# Rectifier.net
KiCad netlist of a schematic drawn in Altium Designer
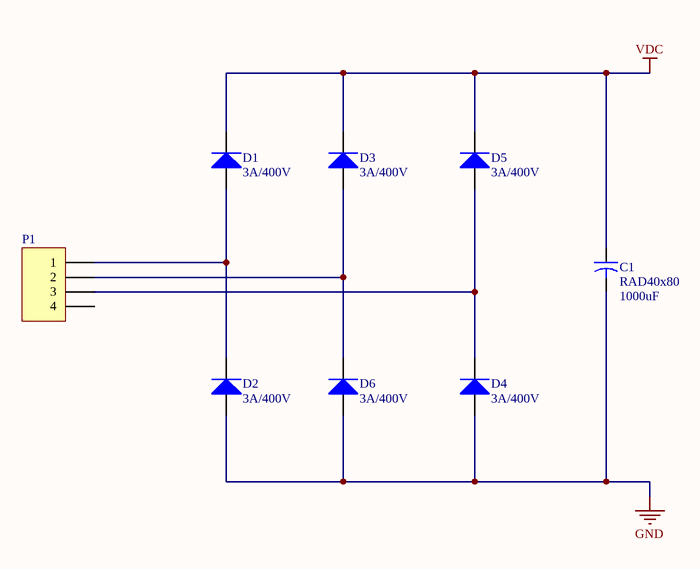
[diagram p0: Rectifier.SchDoc]

(export (version "E")
  (design (tool "Eeschema 10.0.6"))
  (components
    (comp (ref "C1")
      (value "1000uF")
      (footprint "RAD40x80")
      (description "CAP ALUM 1000UF 20% 450V RAD 40X80")
      (fields (field (name "MANUFACTURER") "UNITED CHEMI-CON") (field (name "PACKAGE REFERENCE") "RAD40x80"))
      (libsource (lib "CAPACITOR_LIB") (part "CAP ALUM 1000UF 20% 450V RAD 40X80"))
    )
    (comp (ref "D1")
      (value "3A/400V")
      (footprint "DO201AD")
      (description "DIODE GEN PURP 400V 3A DO201AD")
      (fields
        (field (name "MANUFACTURER") "DIODES INC.")
        (field (name "Comment") "DIODE GEN PURP 400V 3A DO201AD - 1N5404")
      )
      (libsource (lib "DISCRETE_LIB") (part "DIODE GEN PURP 400V 3A DO201AD - 1N5404"))
    )
    (comp (ref "D2")
      (value "3A/400V")
      (footprint "DO201AD")
      (description "DIODE GEN PURP 400V 3A DO201AD")
      (fields
        (field (name "MANUFACTURER") "DIODES INC.")
        (field (name "Comment") "DIODE GEN PURP 400V 3A DO201AD - 1N5404")
      )
      (libsource (lib "DISCRETE_LIB") (part "DIODE GEN PURP 400V 3A DO201AD - 1N5404"))
    )
    (comp (ref "D3")
      (value "3A/400V")
      (footprint "DO201AD")
      (description "DIODE GEN PURP 400V 3A DO201AD")
      (fields
        (field (name "MANUFACTURER") "DIODES INC.")
        (field (name "Comment") "DIODE GEN PURP 400V 3A DO201AD - 1N5404")
      )
      (libsource (lib "DISCRETE_LIB") (part "DIODE GEN PURP 400V 3A DO201AD - 1N5404"))
    )
    (comp (ref "D4")
      (value "3A/400V")
      (footprint "DO201AD")
      (description "DIODE GEN PURP 400V 3A DO201AD")
      (fields
        (field (name "MANUFACTURER") "DIODES INC.")
        (field (name "Comment") "DIODE GEN PURP 400V 3A DO201AD - 1N5404")
      )
      (libsource (lib "DISCRETE_LIB") (part "DIODE GEN PURP 400V 3A DO201AD - 1N5404"))
    )
    (comp (ref "D5")
      (value "3A/400V")
      (footprint "DO201AD")
      (description "DIODE GEN PURP 400V 3A DO201AD")
      (fields
        (field (name "MANUFACTURER") "DIODES INC.")
        (field (name "Comment") "DIODE GEN PURP 400V 3A DO201AD - 1N5404")
      )
      (libsource (lib "DISCRETE_LIB") (part "DIODE GEN PURP 400V 3A DO201AD - 1N5404"))
    )
    (comp (ref "D6")
      (value "3A/400V")
      (footprint "DO201AD")
      (description "DIODE GEN PURP 400V 3A DO201AD")
      (fields
        (field (name "MANUFACTURER") "DIODES INC.")
        (field (name "Comment") "DIODE GEN PURP 400V 3A DO201AD - 1N5404")
      )
      (libsource (lib "DISCRETE_LIB") (part "DIODE GEN PURP 400V 3A DO201AD - 1N5404"))
    )
    (comp (ref "P1")
      (value "CTB9358/4AO")
      (footprint "CTB9350/4AO")
      (description "4 pos plıggable terminal")
      (fields (field (name "PUBLISHER") "Sinan"))
      (libsource (lib "Viva") (part "CTB9358/4AO"))
    )
  )
  (nets
    (net (code "1") (name "GND") (class "Default")
      (node (ref "C1") (pin "2") (pinfunction "2_2") (pintype "passive"))
      (node (ref "D2") (pin "1") (pinfunction "A_1") (pintype "passive"))
      (node (ref "D4") (pin "1") (pinfunction "A_1") (pintype "passive"))
      (node (ref "D6") (pin "1") (pinfunction "A_1") (pintype "passive"))
    )
    (net (code "2") (name "Net-(D1-A)") (class "Default")
      (node (ref "D1") (pin "1") (pinfunction "A_1") (pintype "passive"))
      (node (ref "D2") (pin "2") (pinfunction "K_2") (pintype "passive"))
      (node (ref "P1") (pin "1") (pinfunction "1_1") (pintype "passive"))
    )
    (net (code "3") (name "Net-(D3-A)") (class "Default")
      (node (ref "D3") (pin "1") (pinfunction "A_1") (pintype "passive"))
      (node (ref "D6") (pin "2") (pinfunction "K_2") (pintype "passive"))
      (node (ref "P1") (pin "2") (pinfunction "2_2") (pintype "passive"))
    )
    (net (code "4") (name "Net-(D4-K)") (class "Default")
      (node (ref "D4") (pin "2") (pinfunction "K_2") (pintype "passive"))
      (node (ref "D5") (pin "1") (pinfunction "A_1") (pintype "passive"))
      (node (ref "P1") (pin "3") (pinfunction "3_3") (pintype "passive"))
    )
    (net (code "5") (name "VDC") (class "Default")
      (node (ref "C1") (pin "1") (pinfunction "1_1") (pintype "passive"))
      (node (ref "D1") (pin "2") (pinfunction "K_2") (pintype "passive"))
      (node (ref "D3") (pin "2") (pinfunction "K_2") (pintype "passive"))
      (node (ref "D5") (pin "2") (pinfunction "K_2") (pintype "passive"))
    )
    (net (code "6") (name "unconnected-(P1-Pad4)") (class "Default")
      (node (ref "P1") (pin "4") (pinfunction "4_4") (pintype "passive"))
    )
  )
)
